# Sheet1_28Pin.net
KiCad netlist of a schematic drawn in Altium Designer
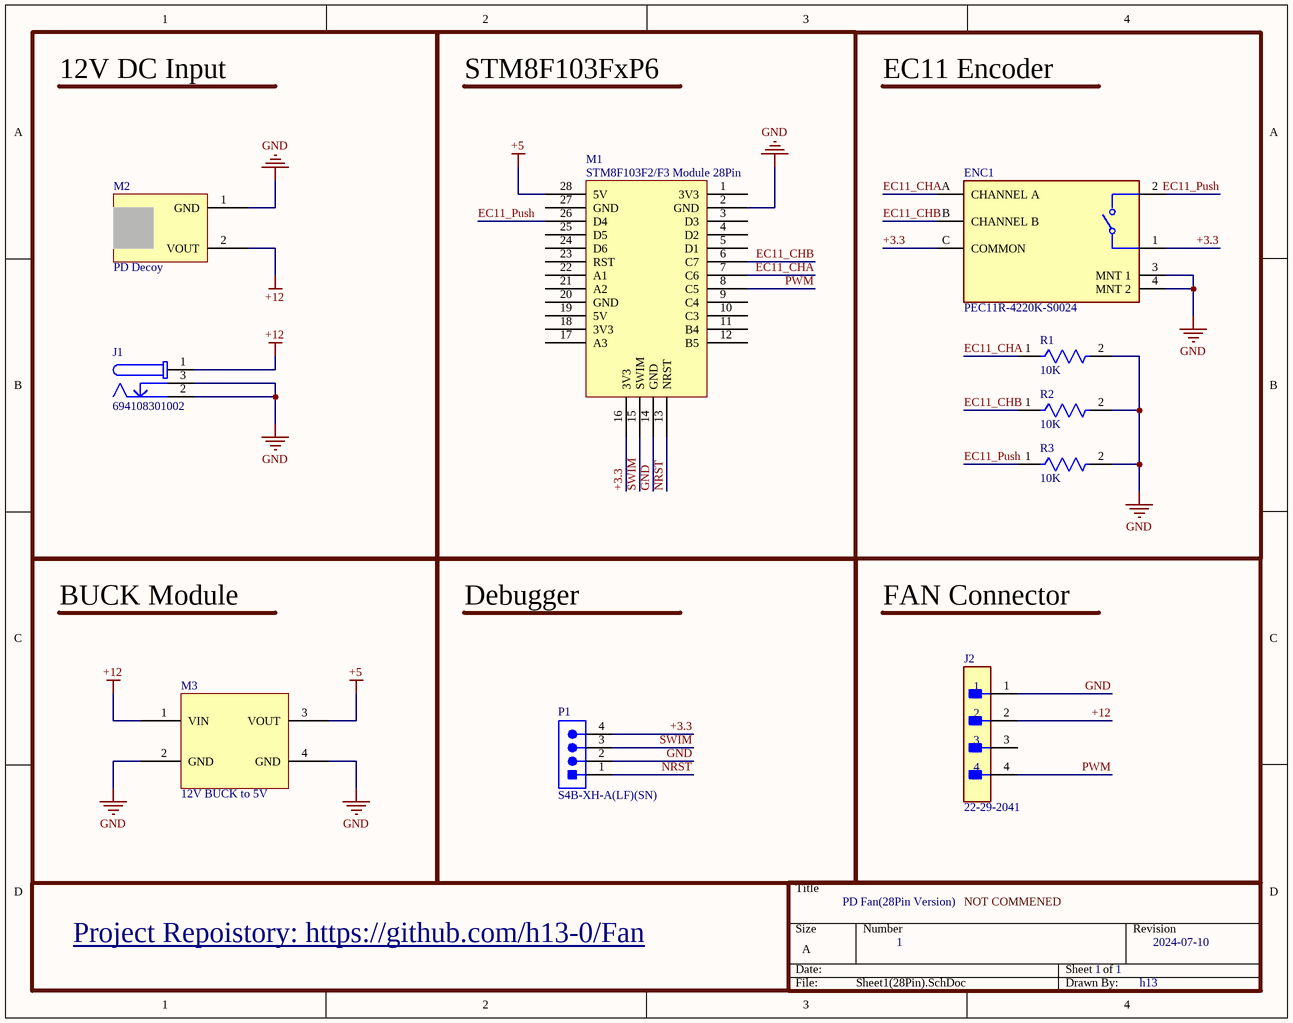
[diagram p0: Sheet1(28Pin).SchDoc]

(export (version "E")
  (design (tool "Eeschema 10.0.6"))
  (components
    (comp (ref "ENC1")
      (value "PEC11R-4220K-S0024")
      (footprint "EC11")
      (description "ROTARY ENCODER INCREMENTAL 24PPR")
      (libsource (lib "Altium Content Vault") (part "d75f9e24c474ed3fe2cf82f27e06f2a"))
    )
    (comp (ref "J1")
      (value "694108301002")
      (footprint "694108301002")
      (libsource (lib "Altium Content Vault") (part "DC Power Jack"))
    )
    (comp (ref "J2")
      (value "22-29-2041")
      (footprint "FP-22-29-2041-MFG")
      (description "CONN HEADER VERT 4POS 2.54MM")
      (libsource (lib "Altium Content Vault") (part "299a8cea1bdcbc3624fe62c390fa72c"))
    )
    (comp (ref "M1")
      (value "STM8F103F2/F3 Module 28Pin")
      (footprint "STM8FxP6 Module 28Pin")
      (libsource (lib "STM8S103F") (part "STM8F103F2/F3 Module 28Pin"))
    )
    (comp (ref "M2") (value "PD Decoy") (footprint "PD Decoy") (libsource (lib "PD_Decoy") (part "PD Decoy")))
    (comp (ref "M3")
      (value "12V BUCK to 5V")
      (footprint "Buck Mini")
      (libsource (lib "BUCK_BOOST") (part "BUCK ¦ BOOST"))
    )
    (comp (ref "P1")
      (value "S4B-XH-A(LF)(SN)")
      (footprint "JST-S4B-XH-A(LF)(SN)_V")
      (libsource (lib "Altium Content Vault") (part "CN-1P-M-R4"))
    )
    (comp (ref "R1")
      (value "10K")
      (footprint "FP-MRS25-MFG")
      (description "RES 1K OHM 0.6W 1% AXIAL")
      (fields (field (name "TOLERANCE") "1%"))
      (libsource (lib "Altium Content Vault") (part "1029c3af85768c4190bb7ad29bc67b5"))
    )
    (comp (ref "R2")
      (value "10K")
      (footprint "FP-MRS25-MFG")
      (description "RES 1K OHM 0.6W 1% AXIAL")
      (fields (field (name "TOLERANCE") "1%"))
      (libsource (lib "Altium Content Vault") (part "1029c3af85768c4190bb7ad29bc67b5"))
    )
    (comp (ref "R3")
      (value "10K")
      (footprint "FP-MRS25-MFG")
      (description "RES 1K OHM 0.6W 1% AXIAL")
      (fields (field (name "TOLERANCE") "1%"))
      (libsource (lib "Altium Content Vault") (part "1029c3af85768c4190bb7ad29bc67b5"))
    )
  )
  (nets
    (net (code "1") (name "+5") (class "Default")
      (node (ref "M1") (pin "28") (pinfunction "5V_28") (pintype "passive"))
      (node (ref "M3") (pin "3") (pinfunction "VOUT_3") (pintype "passive"))
    )
    (net (code "2") (name "+12") (class "Default")
      (node (ref "J1") (pin "1") (pinfunction "1_1") (pintype "passive"))
      (node (ref "J2") (pin "2") (pinfunction "2_2") (pintype "passive"))
      (node (ref "M2") (pin "2") (pinfunction "VOUT_2") (pintype "passive"))
      (node (ref "M3") (pin "1") (pinfunction "VIN_1") (pintype "passive"))
    )
    (net (code "3") (name "/+3.3") (class "Default")
      (node (ref "ENC1") (pin "1") (pinfunction "1_1") (pintype "passive"))
      (node (ref "ENC1") (pin "C") (pinfunction "COMMON_C") (pintype "passive"))
      (node (ref "M1") (pin "16") (pinfunction "3V3_16") (pintype "passive"))
      (node (ref "P1") (pin "4") (pinfunction "4_4") (pintype "passive"))
    )
    (net (code "4") (name "/EC11_CHA") (class "Default")
      (node (ref "ENC1") (pin "A") (pinfunction "CHANNEL_A_A") (pintype "passive"))
      (node (ref "M1") (pin "7") (pinfunction "C6_7") (pintype "passive"))
      (node (ref "R1") (pin "1") (pinfunction "1_1") (pintype "passive"))
    )
    (net (code "5") (name "/EC11_CHB") (class "Default")
      (node (ref "ENC1") (pin "B") (pinfunction "CHANNEL_B_B") (pintype "passive"))
      (node (ref "M1") (pin "6") (pinfunction "C7_6") (pintype "passive"))
      (node (ref "R2") (pin "1") (pinfunction "1_1") (pintype "passive"))
    )
    (net (code "6") (name "/EC11_Push") (class "Default")
      (node (ref "ENC1") (pin "2") (pinfunction "2_2") (pintype "passive"))
      (node (ref "M1") (pin "26") (pinfunction "D4_26") (pintype "passive"))
      (node (ref "R3") (pin "1") (pinfunction "1_1") (pintype "passive"))
    )
    (net (code "7") (name "/NRST") (class "Default")
      (node (ref "M1") (pin "13") (pinfunction "NRST_13") (pintype "passive"))
      (node (ref "P1") (pin "1") (pinfunction "1_1") (pintype "passive"))
    )
    (net (code "8") (name "/PWM") (class "Default")
      (node (ref "J2") (pin "4") (pinfunction "4_4") (pintype "passive"))
      (node (ref "M1") (pin "8") (pinfunction "C5_8") (pintype "passive"))
    )
    (net (code "9") (name "/SWIM") (class "Default")
      (node (ref "M1") (pin "15") (pinfunction "SWIM_15") (pintype "passive"))
      (node (ref "P1") (pin "3") (pinfunction "3_3") (pintype "passive"))
    )
    (net (code "10") (name "GND") (class "Default")
      (node (ref "ENC1") (pin "3") (pinfunction "MNT_1_3") (pintype "passive"))
      (node (ref "ENC1") (pin "4") (pinfunction "MNT_2_4") (pintype "passive"))
      (node (ref "J1") (pin "2") (pinfunction "2_2") (pintype "passive"))
      (node (ref "J1") (pin "3") (pinfunction "3_3") (pintype "passive"))
      (node (ref "J2") (pin "1") (pinfunction "1_1") (pintype "passive"))
      (node (ref "M1") (pin "14") (pinfunction "GND_14") (pintype "passive"))
      (node (ref "M1") (pin "2") (pinfunction "GND_2") (pintype "passive"))
      (node (ref "M2") (pin "1") (pinfunction "GND_1") (pintype "passive"))
      (node (ref "M3") (pin "2") (pinfunction "GND_2") (pintype "passive"))
      (node (ref "M3") (pin "4") (pinfunction "GND_4") (pintype "passive"))
      (node (ref "P1") (pin "2") (pinfunction "2_2") (pintype "passive"))
      (node (ref "R1") (pin "2") (pinfunction "2_2") (pintype "passive"))
      (node (ref "R2") (pin "2") (pinfunction "2_2") (pintype "passive"))
      (node (ref "R3") (pin "2") (pinfunction "2_2") (pintype "passive"))
    )
    (net (code "11") (name "unconnected-(J2-Pad3)") (class "Default")
      (node (ref "J2") (pin "3") (pinfunction "3_3") (pintype "passive"))
    )
    (net (code "12") (name "unconnected-(M1-3V3-Pad1)") (class "Default")
      (node (ref "M1") (pin "1") (pinfunction "3V3_1") (pintype "passive"))
    )
    (net (code "13") (name "unconnected-(M1-3V3-Pad18)") (class "Default")
      (node (ref "M1") (pin "18") (pinfunction "3V3_18") (pintype "passive"))
    )
    (net (code "14") (name "unconnected-(M1-5V-Pad19)") (class "Default")
      (node (ref "M1") (pin "19") (pinfunction "5V_19") (pintype "passive"))
    )
    (net (code "15") (name "unconnected-(M1-A1-Pad22)") (class "Default")
      (node (ref "M1") (pin "22") (pinfunction "A1_22") (pintype "passive"))
    )
    (net (code "16") (name "unconnected-(M1-A2-Pad21)") (class "Default")
      (node (ref "M1") (pin "21") (pinfunction "A2_21") (pintype "passive"))
    )
    (net (code "17") (name "unconnected-(M1-A3-Pad17)") (class "Default")
      (node (ref "M1") (pin "17") (pinfunction "A3_17") (pintype "passive"))
    )
    (net (code "18") (name "unconnected-(M1-B4-Pad11)") (class "Default")
      (node (ref "M1") (pin "11") (pinfunction "B4_11") (pintype "passive"))
    )
    (net (code "19") (name "unconnected-(M1-B5-Pad12)") (class "Default")
      (node (ref "M1") (pin "12") (pinfunction "B5_12") (pintype "passive"))
    )
    (net (code "20") (name "unconnected-(M1-C3-Pad10)") (class "Default")
      (node (ref "M1") (pin "10") (pinfunction "C3_10") (pintype "passive"))
    )
    (net (code "21") (name "unconnected-(M1-C4-Pad9)") (class "Default")
      (node (ref "M1") (pin "9") (pinfunction "C4_9") (pintype "passive"))
    )
    (net (code "22") (name "unconnected-(M1-D1-Pad5)") (class "Default")
      (node (ref "M1") (pin "5") (pinfunction "D1_5") (pintype "passive"))
    )
    (net (code "23") (name "unconnected-(M1-D2-Pad4)") (class "Default")
      (node (ref "M1") (pin "4") (pinfunction "D2_4") (pintype "passive"))
    )
    (net (code "24") (name "unconnected-(M1-D3-Pad3)") (class "Default")
      (node (ref "M1") (pin "3") (pinfunction "D3_3") (pintype "passive"))
    )
    (net (code "25") (name "unconnected-(M1-D5-Pad25)") (class "Default")
      (node (ref "M1") (pin "25") (pinfunction "D5_25") (pintype "passive"))
    )
    (net (code "26") (name "unconnected-(M1-D6-Pad24)") (class "Default")
      (node (ref "M1") (pin "24") (pinfunction "D6_24") (pintype "passive"))
    )
    (net (code "27") (name "unconnected-(M1-GND-Pad20)") (class "Default")
      (node (ref "M1") (pin "20") (pinfunction "GND_20") (pintype "passive"))
    )
    (net (code "28") (name "unconnected-(M1-GND-Pad27)") (class "Default")
      (node (ref "M1") (pin "27") (pinfunction "GND_27") (pintype "passive"))
    )
    (net (code "29") (name "unconnected-(M1-RST-Pad23)") (class "Default")
      (node (ref "M1") (pin "23") (pinfunction "RST_23") (pintype "passive"))
    )
  )
)
